# AirControl.net
KiCad netlist of a schematic drawn in EAGLE
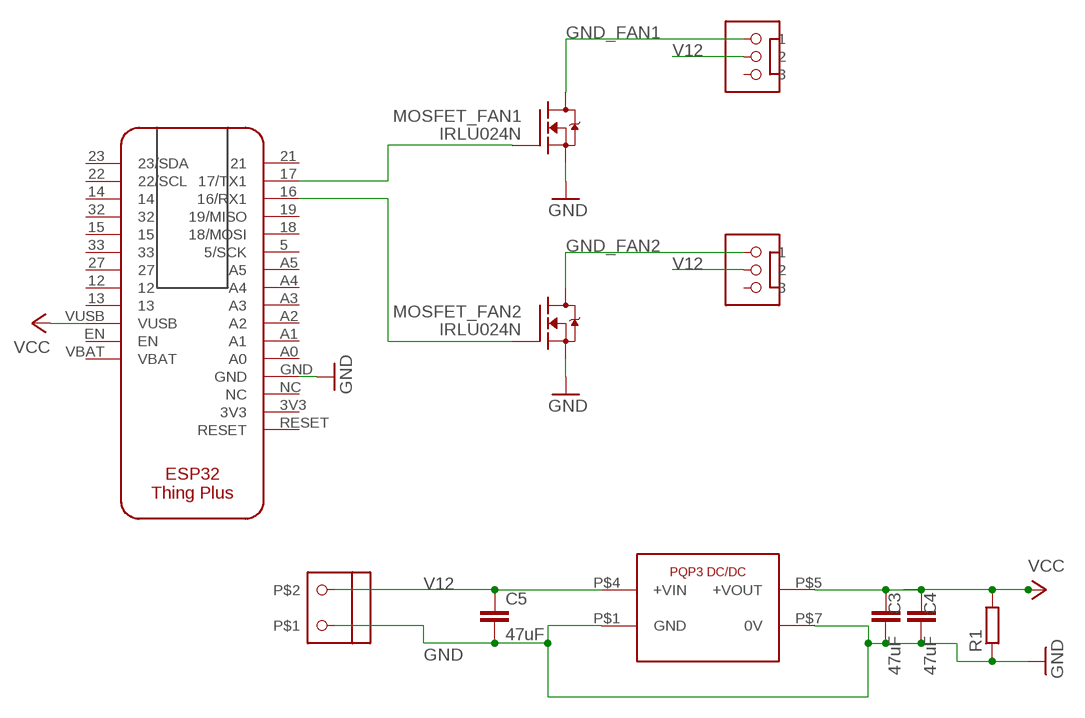
[diagram p0: schematic, sheet 1]

(export (version "E")
  (design (tool "Eeschema 10.0.6"))
  (components
    (comp (ref "C3")
      (value "47uF")
      (footprint "eagle-import:C1210")
      (libsource (lib "eagle-import") (part "C-EUC1210"))
    )
    (comp (ref "C4")
      (value "47uF")
      (footprint "eagle-import:C1210")
      (libsource (lib "eagle-import") (part "C-EUC1210"))
    )
    (comp (ref "C5")
      (value "47uF")
      (footprint "eagle-import:C1210")
      (libsource (lib "eagle-import") (part "C-EUC1210"))
    )
    (comp (ref "MOSFET_FAN1")
      (value "IRLU024N")
      (footprint "eagle-import:TO220-STANDING")
      (libsource (lib "eagle-import") (part "IRLU024N"))
    )
    (comp (ref "MOSFET_FAN2")
      (value "IRLU024N")
      (footprint "eagle-import:TO220-STANDING")
      (libsource (lib "eagle-import") (part "IRLU024N"))
    )
    (comp (ref "PQP3")
      (value "PQP3-D12-S5-DPQP3--D12-S5-D")
      (footprint "eagle-import:PQP3-D")
      (libsource (lib "eagle-import") (part "PQP3-D12-S5-DPQP3--D12-S5-D"))
    )
    (comp (ref "R1")
      (value "R-EU_R1210")
      (footprint "eagle-import:R1210")
      (libsource (lib "eagle-import") (part "R-EU_R1210"))
    )
    (comp (ref "U$2")
      (value "THING_PLUSTHING_PLUS")
      (footprint "eagle-import:THING_PLUS")
      (libsource (lib "eagle-import") (part "THING_PLUSTHING_PLUS"))
    )
    (comp (ref "U$3")
      (value "MOLEX_22-27-2031")
      (footprint "eagle-import:MOLEX_22-27-2031")
      (libsource (lib "eagle-import") (part "MOLEX_22-27-2031"))
    )
    (comp (ref "U$4")
      (value "MOLEX_22-27-2031")
      (footprint "eagle-import:MOLEX_22-27-2031")
      (libsource (lib "eagle-import") (part "MOLEX_22-27-2031"))
    )
    (comp (ref "U$5")
      (value "AKL012-02")
      (footprint "eagle-import:AKL012-02")
      (libsource (lib "eagle-import") (part "AKL012-02"))
    )
  )
  (nets
    (net (code "1") (name "/GND_FAN1") (class "Default")
      (node (ref "MOSFET_FAN1") (pin "2") (pinfunction "D_2") (pintype "passive"))
      (node (ref "U$3") (pin "P$1") (pinfunction "1_P$1") (pintype "bidirectional"))
    )
    (net (code "2") (name "/GND_FAN2") (class "Default")
      (node (ref "MOSFET_FAN2") (pin "2") (pinfunction "D_2") (pintype "passive"))
      (node (ref "U$4") (pin "P$1") (pinfunction "1_P$1") (pintype "bidirectional"))
    )
    (net (code "3") (name "/V12") (class "Default")
      (node (ref "C5") (pin "1") (pinfunction "1_1") (pintype "passive"))
      (node (ref "PQP3") (pin "P$4") (pinfunction "+VIN_P$4") (pintype "bidirectional"))
      (node (ref "U$3") (pin "P$2") (pinfunction "2_P$2") (pintype "bidirectional"))
      (node (ref "U$4") (pin "P$2") (pinfunction "2_P$2") (pintype "bidirectional"))
      (node (ref "U$5") (pin "P$2") (pinfunction "P$2_P$2") (pintype "bidirectional"))
    )
    (net (code "4") (name "GND") (class "Default")
      (node (ref "C3") (pin "2") (pinfunction "2_2") (pintype "passive"))
      (node (ref "C4") (pin "2") (pinfunction "2_2") (pintype "passive"))
      (node (ref "C5") (pin "2") (pinfunction "2_2") (pintype "passive"))
      (node (ref "MOSFET_FAN1") (pin "3") (pinfunction "S_3") (pintype "passive"))
      (node (ref "MOSFET_FAN2") (pin "3") (pinfunction "S_3") (pintype "passive"))
      (node (ref "PQP3") (pin "P$1") (pinfunction "GND_P$1") (pintype "bidirectional"))
      (node (ref "PQP3") (pin "P$7") (pinfunction "0V_P$7") (pintype "bidirectional"))
      (node (ref "R1") (pin "1") (pinfunction "1_1") (pintype "passive"))
      (node (ref "U$2") (pin "GND") (pinfunction "GND_GND") (pintype "bidirectional"))
      (node (ref "U$5") (pin "P$1") (pinfunction "P$1_P$1") (pintype "bidirectional"))
    )
    (net (code "5") (name "Net-(MOSFET_FAN1-G)") (class "Default")
      (node (ref "MOSFET_FAN1") (pin "1") (pinfunction "G_1") (pintype "passive"))
      (node (ref "U$2") (pin "17") (pinfunction "17/TX1_17") (pintype "bidirectional"))
    )
    (net (code "6") (name "Net-(MOSFET_FAN2-G)") (class "Default")
      (node (ref "MOSFET_FAN2") (pin "1") (pinfunction "G_1") (pintype "passive"))
      (node (ref "U$2") (pin "16") (pinfunction "16/RX1_16") (pintype "bidirectional"))
    )
    (net (code "7") (name "VCC") (class "Default")
      (node (ref "C3") (pin "1") (pinfunction "1_1") (pintype "passive"))
      (node (ref "C4") (pin "1") (pinfunction "1_1") (pintype "passive"))
      (node (ref "PQP3") (pin "P$5") (pinfunction "+VOUT_P$5") (pintype "bidirectional"))
      (node (ref "R1") (pin "2") (pinfunction "2_2") (pintype "passive"))
      (node (ref "U$2") (pin "VUSB") (pinfunction "VUSB_VUSB") (pintype "bidirectional"))
    )
    (net (code "8") (name "unconnected-(U$2-5{slash}SCK-Pad5)") (class "Default")
      (node (ref "U$2") (pin "5") (pinfunction "5/SCK_5") (pintype "bidirectional"))
    )
    (net (code "9") (name "unconnected-(U$2-18{slash}MOSI-Pad18)") (class "Default")
      (node (ref "U$2") (pin "18") (pinfunction "18/MOSI_18") (pintype "bidirectional"))
    )
    (net (code "10") (name "unconnected-(U$2-19{slash}MISO-Pad19)") (class "Default")
      (node (ref "U$2") (pin "19") (pinfunction "19/MISO_19") (pintype "bidirectional"))
    )
    (net (code "11") (name "unconnected-(U$2-22{slash}SCL-Pad22)") (class "Default")
      (node (ref "U$2") (pin "22") (pinfunction "22/SCL_22") (pintype "bidirectional"))
    )
    (net (code "12") (name "unconnected-(U$2-23{slash}SDA-Pad23)") (class "Default")
      (node (ref "U$2") (pin "23") (pinfunction "23/SDA_23") (pintype "bidirectional"))
    )
    (net (code "13") (name "unconnected-(U$2-Pad3V3)") (class "Default")
      (node (ref "U$2") (pin "3V3") (pinfunction "3V3_3V3") (pintype "bidirectional"))
    )
    (net (code "14") (name "unconnected-(U$2-Pad12)") (class "Default")
      (node (ref "U$2") (pin "12") (pinfunction "12_12") (pintype "bidirectional"))
    )
    (net (code "15") (name "unconnected-(U$2-Pad13)") (class "Default")
      (node (ref "U$2") (pin "13") (pinfunction "13_13") (pintype "bidirectional"))
    )
    (net (code "16") (name "unconnected-(U$2-Pad14)") (class "Default")
      (node (ref "U$2") (pin "14") (pinfunction "14_14") (pintype "bidirectional"))
    )
    (net (code "17") (name "unconnected-(U$2-Pad15)") (class "Default")
      (node (ref "U$2") (pin "15") (pinfunction "15_15") (pintype "bidirectional"))
    )
    (net (code "18") (name "unconnected-(U$2-Pad21)") (class "Default")
      (node (ref "U$2") (pin "21") (pinfunction "21_21") (pintype "bidirectional"))
    )
    (net (code "19") (name "unconnected-(U$2-Pad27)") (class "Default")
      (node (ref "U$2") (pin "27") (pinfunction "27_27") (pintype "bidirectional"))
    )
    (net (code "20") (name "unconnected-(U$2-Pad32)") (class "Default")
      (node (ref "U$2") (pin "32") (pinfunction "32_32") (pintype "bidirectional"))
    )
    (net (code "21") (name "unconnected-(U$2-Pad33)") (class "Default")
      (node (ref "U$2") (pin "33") (pinfunction "33_33") (pintype "bidirectional"))
    )
    (net (code "22") (name "unconnected-(U$2-PadA0)") (class "Default")
      (node (ref "U$2") (pin "A0") (pinfunction "A0_A0") (pintype "bidirectional"))
    )
    (net (code "23") (name "unconnected-(U$2-PadA1)") (class "Default")
      (node (ref "U$2") (pin "A1") (pinfunction "A1_A1") (pintype "bidirectional"))
    )
    (net (code "24") (name "unconnected-(U$2-PadA2)") (class "Default")
      (node (ref "U$2") (pin "A2") (pinfunction "A2_A2") (pintype "bidirectional"))
    )
    (net (code "25") (name "unconnected-(U$2-PadA3)") (class "Default")
      (node (ref "U$2") (pin "A3") (pinfunction "A3_A3") (pintype "bidirectional"))
    )
    (net (code "26") (name "unconnected-(U$2-PadA4)") (class "Default")
      (node (ref "U$2") (pin "A4") (pinfunction "A4_A4") (pintype "bidirectional"))
    )
    (net (code "27") (name "unconnected-(U$2-PadA5)") (class "Default")
      (node (ref "U$2") (pin "A5") (pinfunction "A5_A5") (pintype "bidirectional"))
    )
    (net (code "28") (name "unconnected-(U$2-PadEN)") (class "Default")
      (node (ref "U$2") (pin "EN") (pinfunction "EN_EN") (pintype "bidirectional"))
    )
    (net (code "29") (name "unconnected-(U$2-PadNC)") (class "Default")
      (node (ref "U$2") (pin "NC") (pinfunction "NC_NC") (pintype "bidirectional"))
    )
    (net (code "30") (name "unconnected-(U$2-PadRESET)") (class "Default")
      (node (ref "U$2") (pin "RESET") (pinfunction "RESET_RESET") (pintype "bidirectional"))
    )
    (net (code "31") (name "unconnected-(U$2-PadVBAT)") (class "Default")
      (node (ref "U$2") (pin "VBAT") (pinfunction "VBAT_VBAT") (pintype "bidirectional"))
    )
    (net (code "32") (name "unconnected-(U$3-3-PadP$3)") (class "Default")
      (node (ref "U$3") (pin "P$3") (pinfunction "3_P$3") (pintype "bidirectional"))
    )
    (net (code "33") (name "unconnected-(U$4-3-PadP$3)") (class "Default")
      (node (ref "U$4") (pin "P$3") (pinfunction "3_P$3") (pintype "bidirectional"))
    )
  )
)
